# Grove_-_3-Axis_Digital_Compass_v1_2.net
KiCad netlist of a schematic drawn in EAGLE
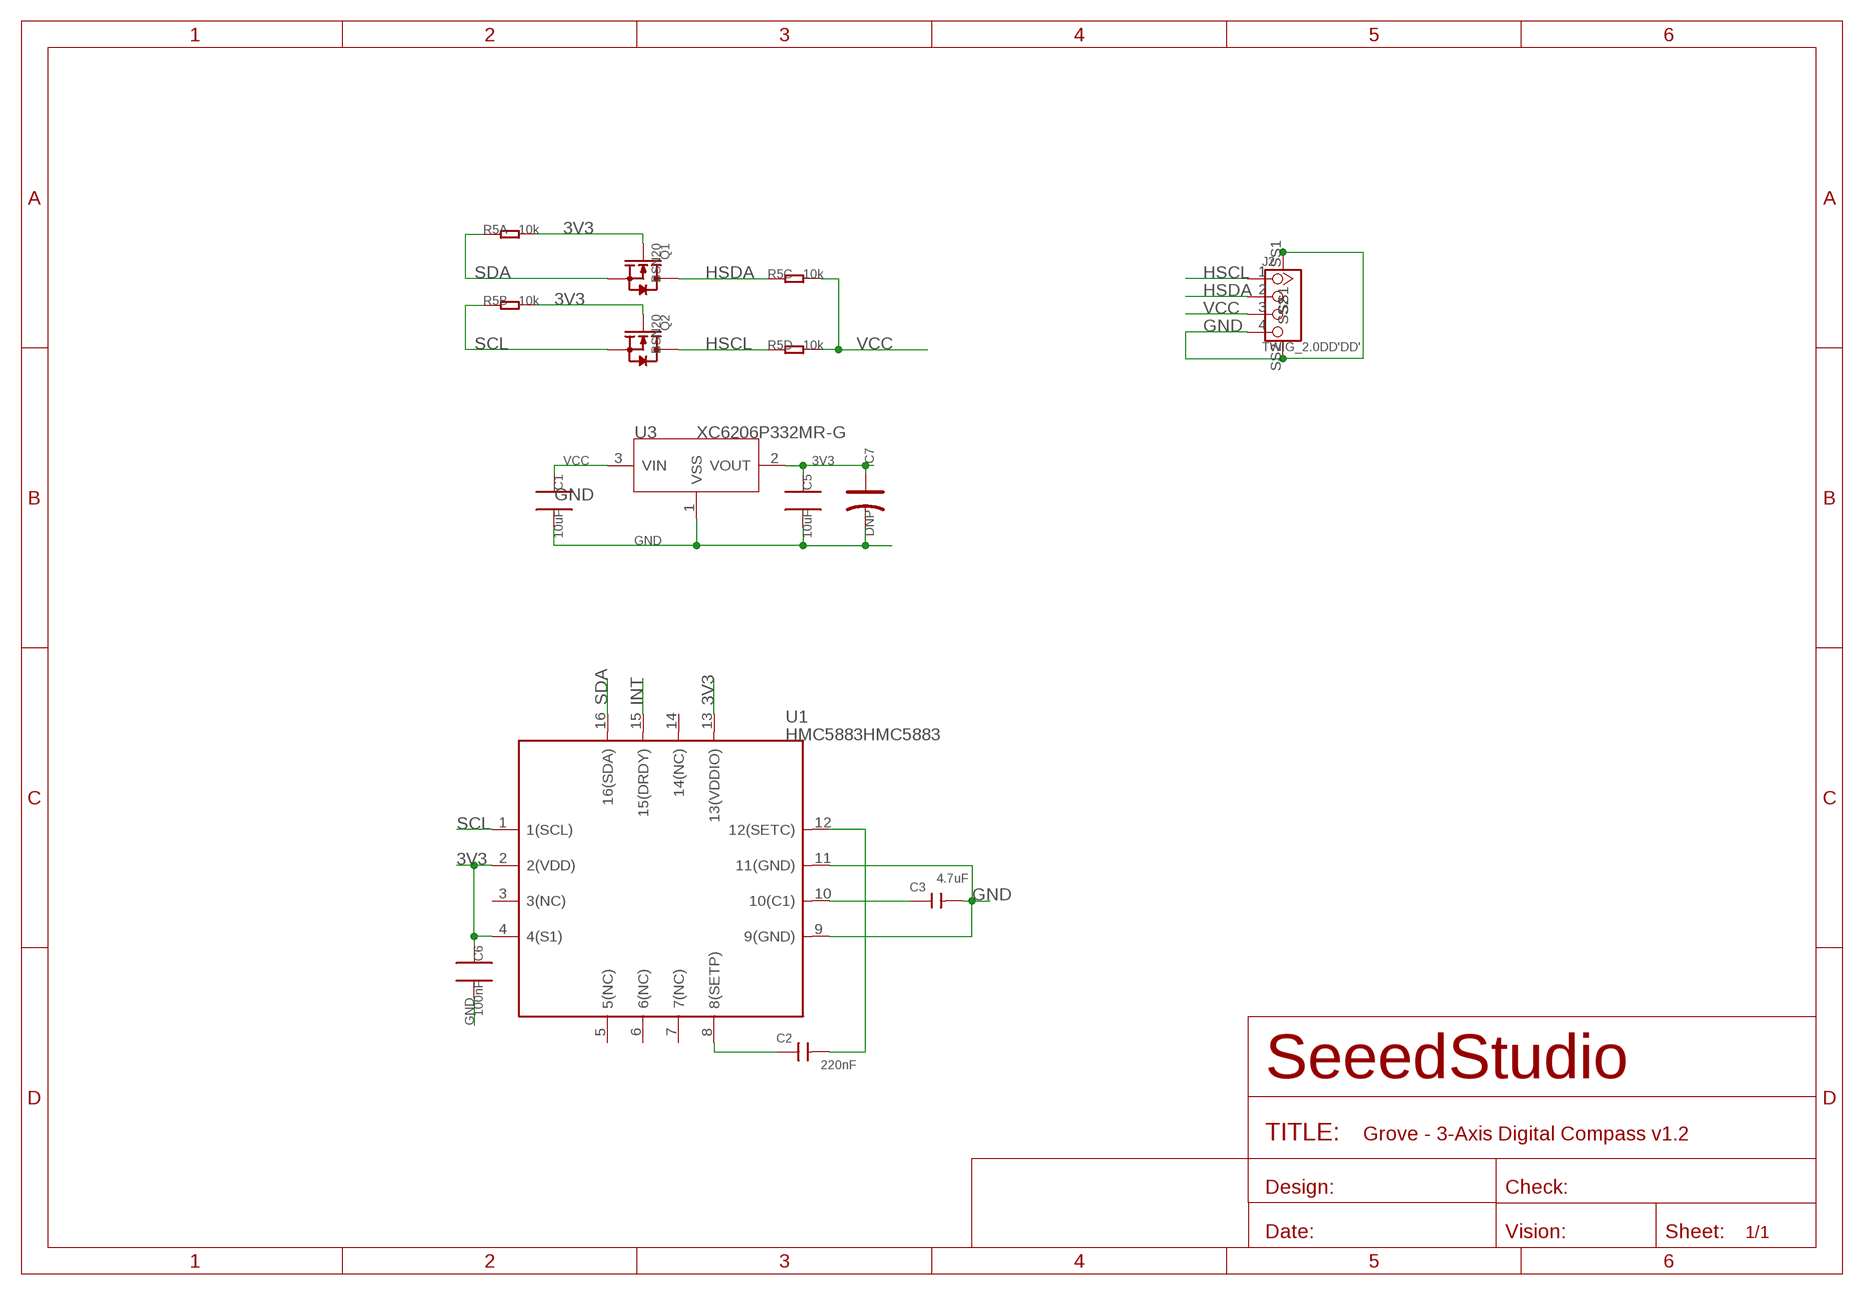
[diagram p0: schematic, sheet 1]

(export (version "E")
  (design (tool "Eeschema 10.0.6"))
  (components
    (comp (ref "C1")
      (value "10uF")
      (footprint "eagle-import:0805_S")
      (libsource (lib "eagle-import") (part "C0805_S"))
    )
    (comp (ref "C2")
      (value "220nF")
      (footprint "eagle-import:0603_S")
      (libsource (lib "eagle-import") (part "006-C3035"))
    )
    (comp (ref "C3")
      (value "4.7uF")
      (footprint "eagle-import:C0805")
      (libsource (lib "eagle-import") (part "C-0805"))
    )
    (comp (ref "C5")
      (value "10uF")
      (footprint "eagle-import:0805_S")
      (libsource (lib "eagle-import") (part "C0805_S"))
    )
    (comp (ref "C6")
      (value "100nF")
      (footprint "eagle-import:0603_S")
      (libsource (lib "eagle-import") (part "C0603_S"))
    )
    (comp (ref "C7")
      (value "DNP")
      (footprint "eagle-import:AVX-A")
      (libsource (lib "eagle-import") (part "CAP-AVX-A"))
    )
    (comp (ref "J2")
      (value "TWIG_2.0DD'DD'")
      (footprint "eagle-import:2.0_1X4DD")
      (libsource (lib "eagle-import") (part "TWIG_2.0DD'DD'"))
    )
    (comp (ref "Q1")
      (value "BSN20")
      (footprint "eagle-import:SOT23")
      (libsource (lib "eagle-import") (part "MOSFET-N'SOT23'"))
    )
    (comp (ref "Q2")
      (value "BSN20")
      (footprint "eagle-import:SOT23")
      (libsource (lib "eagle-import") (part "MOSFET-N'SOT23'"))
    )
    (comp (ref "R5")
      (value "10k")
      (footprint "eagle-import:R1206-8")
      (libsource (lib "eagle-import") (part "005-4R_1206"))
    )
    (comp (ref "U1")
      (value "HMC5883HMC5883")
      (footprint "eagle-import:HMC5883")
      (libsource (lib "eagle-import") (part "HMC5883HMC5883"))
    )
    (comp (ref "U3")
      (value "XC6206P332MR-G")
      (footprint "eagle-import:SOT23")
      (libsource (lib "eagle-import") (part "XC6206MR"))
    )
  )
  (nets
    (net (code "1") (name "/3V3") (class "Default")
      (node (ref "C5") (pin "1") (pinfunction "1_1") (pintype "bidirectional"))
      (node (ref "C6") (pin "1") (pinfunction "1_1") (pintype "bidirectional"))
      (node (ref "C7") (pin "+") (pinfunction "+_+") (pintype "passive"))
      (node (ref "Q1") (pin "1") (pinfunction "G_1") (pintype "passive"))
      (node (ref "Q2") (pin "1") (pinfunction "G_1") (pintype "passive"))
      (node (ref "R5") (pin "7") (pinfunction "2_7") (pintype "passive"))
      (node (ref "R5") (pin "8") (pinfunction "2_8") (pintype "passive"))
      (node (ref "U1") (pin "13") (pinfunction "13(VDDIO)_13") (pintype "power_in"))
      (node (ref "U1") (pin "2") (pinfunction "2(VDD)_2") (pintype "power_in"))
      (node (ref "U1") (pin "4") (pinfunction "4(S1)_4") (pintype "bidirectional"))
      (node (ref "U3") (pin "2") (pinfunction "VOUT_2") (pintype "output"))
    )
    (net (code "2") (name "/GND") (class "Default")
      (node (ref "C1") (pin "2") (pinfunction "2_2") (pintype "bidirectional"))
      (node (ref "C3") (pin "2") (pinfunction "2_2") (pintype "passive"))
      (node (ref "C5") (pin "2") (pinfunction "2_2") (pintype "bidirectional"))
      (node (ref "C6") (pin "2") (pinfunction "2_2") (pintype "bidirectional"))
      (node (ref "C7") (pin "-") (pinfunction "-_-") (pintype "passive"))
      (node (ref "J2") (pin "4") (pinfunction "4_4") (pintype "bidirectional"))
      (node (ref "J2") (pin "SS1") (pinfunction "SS1_SS1") (pintype "bidirectional"))
      (node (ref "J2") (pin "SS2") (pinfunction "SS2_SS2") (pintype "bidirectional"))
      (node (ref "U1") (pin "11") (pinfunction "11(GND)_11") (pintype "power_in"))
      (node (ref "U1") (pin "9") (pinfunction "9(GND)_9") (pintype "power_in"))
      (node (ref "U3") (pin "1") (pinfunction "VSS_1") (pintype "power_in"))
    )
    (net (code "3") (name "/HSCL") (class "Default")
      (node (ref "J2") (pin "1") (pinfunction "1_1") (pintype "bidirectional"))
      (node (ref "Q2") (pin "3") (pinfunction "D_3") (pintype "passive"))
      (node (ref "R5") (pin "4") (pinfunction "1_4") (pintype "passive"))
    )
    (net (code "4") (name "/HSDA") (class "Default")
      (node (ref "J2") (pin "2") (pinfunction "2_2") (pintype "bidirectional"))
      (node (ref "Q1") (pin "3") (pinfunction "D_3") (pintype "passive"))
      (node (ref "R5") (pin "3") (pinfunction "1_3") (pintype "passive"))
    )
    (net (code "5") (name "/INT") (class "Default")
      (node (ref "U1") (pin "15") (pinfunction "15(DRDY)_15") (pintype "bidirectional"))
    )
    (net (code "6") (name "/SCL") (class "Default")
      (node (ref "Q2") (pin "2") (pinfunction "S_2") (pintype "passive"))
      (node (ref "R5") (pin "2") (pinfunction "1_2") (pintype "passive"))
      (node (ref "U1") (pin "1") (pinfunction "1(SCL)_1") (pintype "bidirectional"))
    )
    (net (code "7") (name "/SDA") (class "Default")
      (node (ref "Q1") (pin "2") (pinfunction "S_2") (pintype "passive"))
      (node (ref "R5") (pin "1") (pinfunction "1_1") (pintype "passive"))
      (node (ref "U1") (pin "16") (pinfunction "16(SDA)_16") (pintype "bidirectional"))
    )
    (net (code "8") (name "/VCC") (class "Default")
      (node (ref "C1") (pin "1") (pinfunction "1_1") (pintype "bidirectional"))
      (node (ref "J2") (pin "3") (pinfunction "3_3") (pintype "bidirectional"))
      (node (ref "R5") (pin "5") (pinfunction "2_5") (pintype "passive"))
      (node (ref "R5") (pin "6") (pinfunction "2_6") (pintype "passive"))
      (node (ref "U3") (pin "3") (pinfunction "VIN_3") (pintype "input"))
    )
    (net (code "9") (name "Net-(U1-8(SETP))") (class "Default")
      (node (ref "C2") (pin "1") (pinfunction "1_1") (pintype "passive"))
      (node (ref "U1") (pin "8") (pinfunction "8(SETP)_8") (pintype "bidirectional"))
    )
    (net (code "10") (name "Net-(U1-10(C1))") (class "Default")
      (node (ref "C3") (pin "1") (pinfunction "1_1") (pintype "passive"))
      (node (ref "U1") (pin "10") (pinfunction "10(C1)_10") (pintype "bidirectional"))
    )
    (net (code "11") (name "Net-(U1-12(SETC))") (class "Default")
      (node (ref "C2") (pin "2") (pinfunction "2_2") (pintype "passive"))
      (node (ref "U1") (pin "12") (pinfunction "12(SETC)_12") (pintype "bidirectional"))
    )
    (net (code "12") (name "unconnected-(U1-3(NC)-Pad3)") (class "Default")
      (node (ref "U1") (pin "3") (pinfunction "3(NC)_3") (pintype "no_connect"))
    )
    (net (code "13") (name "unconnected-(U1-5(NC)-Pad5)") (class "Default")
      (node (ref "U1") (pin "5") (pinfunction "5(NC)_5") (pintype "no_connect"))
    )
    (net (code "14") (name "unconnected-(U1-6(NC)-Pad6)") (class "Default")
      (node (ref "U1") (pin "6") (pinfunction "6(NC)_6") (pintype "no_connect"))
    )
    (net (code "15") (name "unconnected-(U1-7(NC)-Pad7)") (class "Default")
      (node (ref "U1") (pin "7") (pinfunction "7(NC)_7") (pintype "no_connect"))
    )
    (net (code "16") (name "unconnected-(U1-14(NC)-Pad14)") (class "Default")
      (node (ref "U1") (pin "14") (pinfunction "14(NC)_14") (pintype "no_connect"))
    )
  )
)
